# M510A.net
KiCad netlist of a schematic drawn in EAGLE
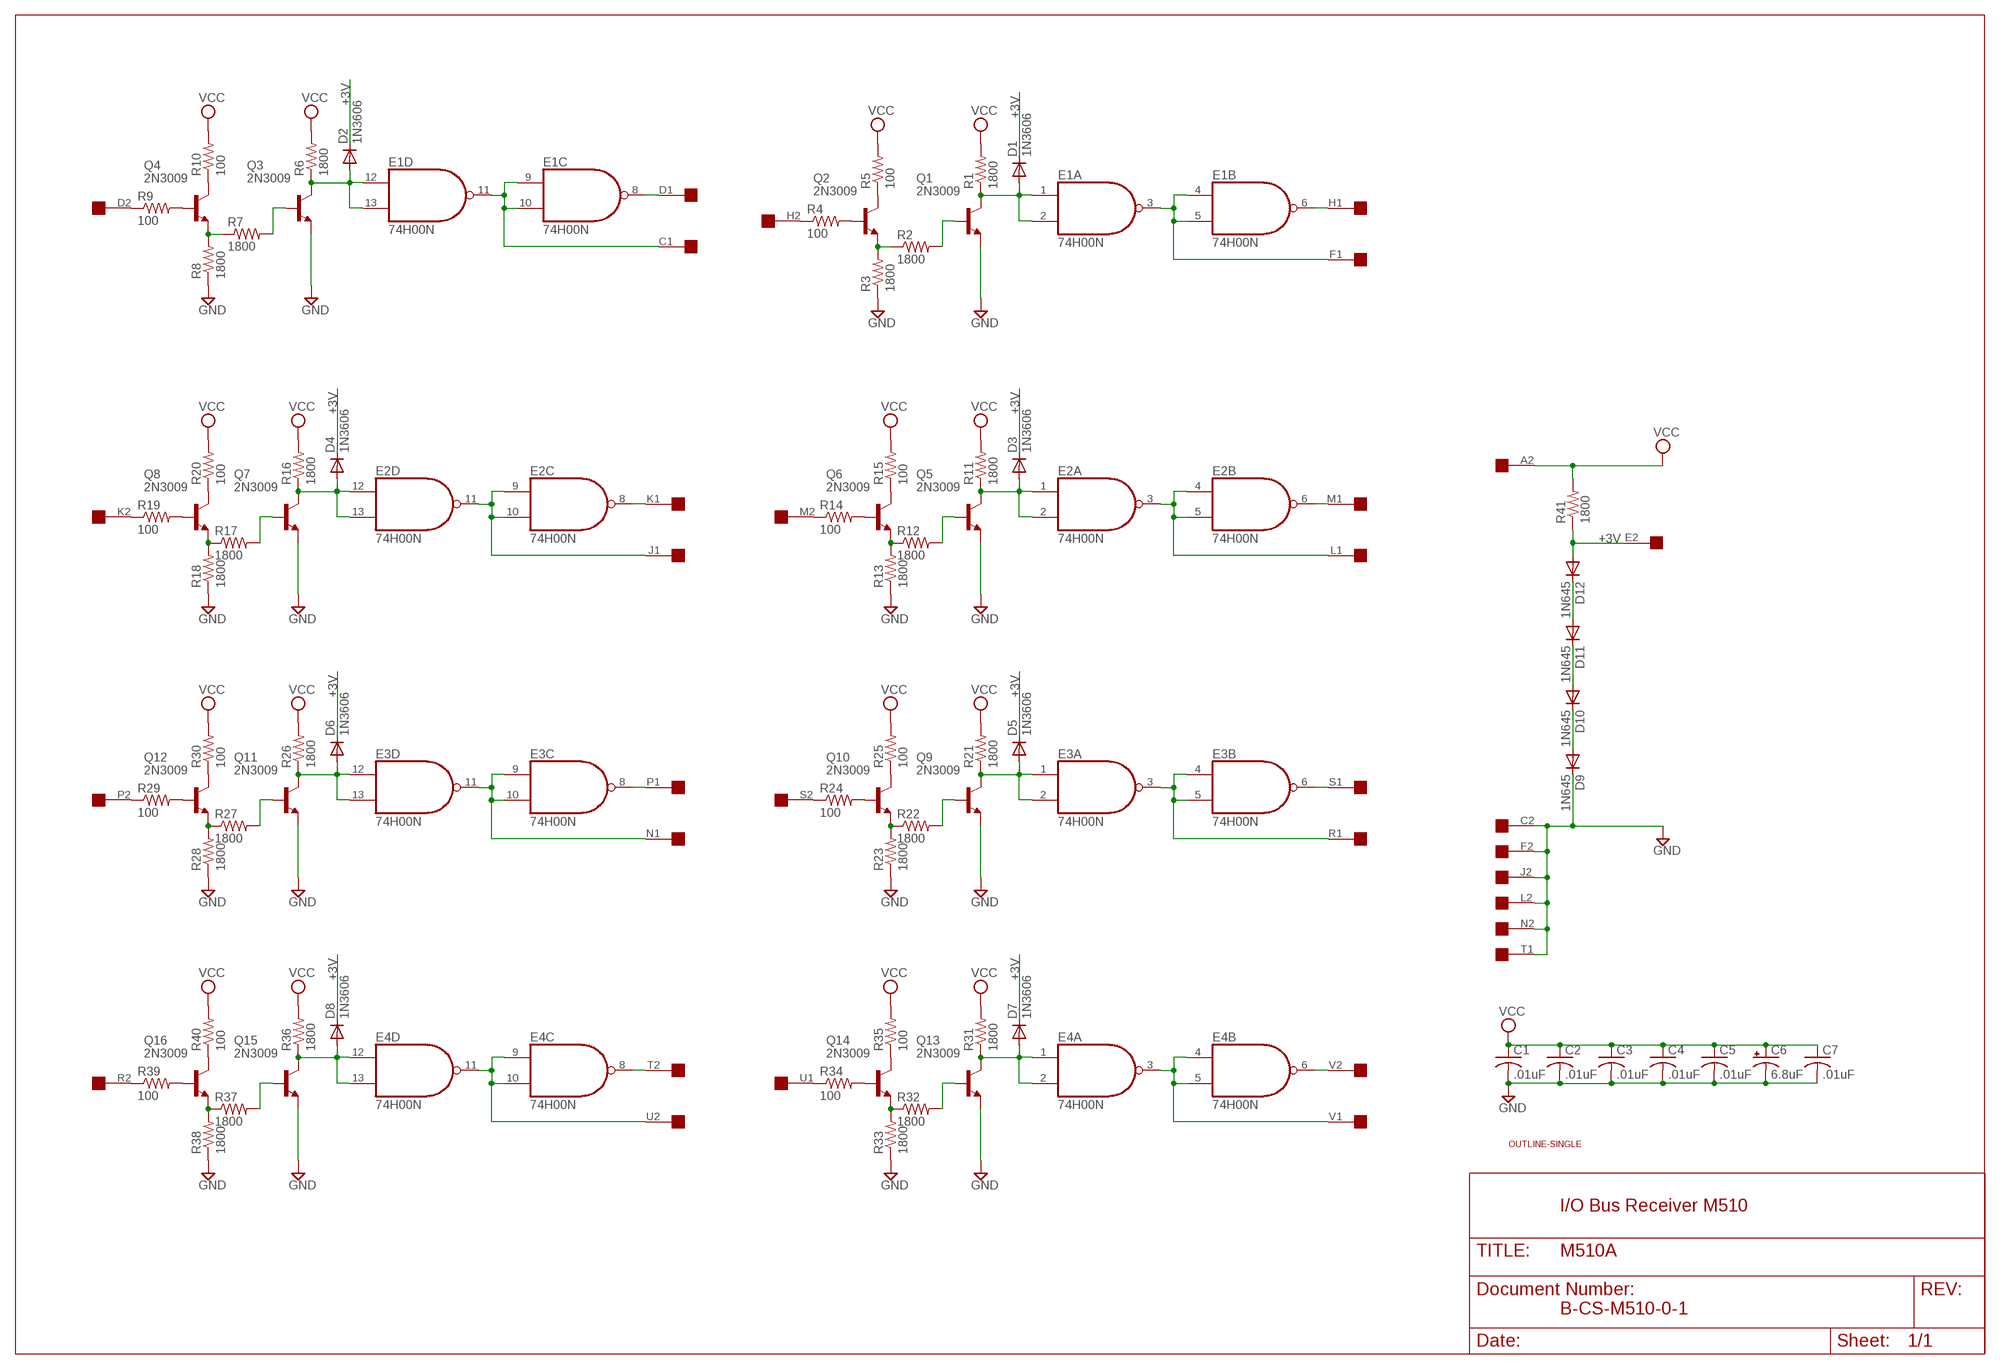
[diagram p0: schematic, sheet 1]

(export (version "E")
  (design (tool "Eeschema 10.0.6"))
  (components
    (comp (ref "C1")
      (value ".01uF")
      (footprint "eagle-import:C050-025X075")
      (libsource (lib "eagle-import") (part "C-US050-025X075"))
    )
    (comp (ref "C2")
      (value ".01uF")
      (footprint "eagle-import:C050-025X075")
      (libsource (lib "eagle-import") (part "C-US050-025X075"))
    )
    (comp (ref "C3")
      (value ".01uF")
      (footprint "eagle-import:C050-025X075")
      (libsource (lib "eagle-import") (part "C-US050-025X075"))
    )
    (comp (ref "C4")
      (value ".01uF")
      (footprint "eagle-import:C050-025X075")
      (libsource (lib "eagle-import") (part "C-US050-025X075"))
    )
    (comp (ref "C5")
      (value ".01uF")
      (footprint "eagle-import:C050-025X075")
      (libsource (lib "eagle-import") (part "C-US050-025X075"))
    )
    (comp (ref "C6")
      (value "6.8uF")
      (footprint "eagle-import:E12-8")
      (libsource (lib "eagle-import") (part "CPOL-USE20-8AXIAL"))
    )
    (comp (ref "C7")
      (value ".01uF")
      (footprint "eagle-import:C050-025X075")
      (libsource (lib "eagle-import") (part "C-US050-025X075"))
    )
    (comp (ref "D1")
      (value "1N3606")
      (footprint "eagle-import:DO35-10")
      (libsource (lib "eagle-import") (part "1N4148DO35-10"))
    )
    (comp (ref "D2")
      (value "1N3606")
      (footprint "eagle-import:DO35-10")
      (libsource (lib "eagle-import") (part "1N4148DO35-10"))
    )
    (comp (ref "D3")
      (value "1N3606")
      (footprint "eagle-import:DO35-10")
      (libsource (lib "eagle-import") (part "1N4148DO35-10"))
    )
    (comp (ref "D4")
      (value "1N3606")
      (footprint "eagle-import:DO35-10")
      (libsource (lib "eagle-import") (part "1N4148DO35-10"))
    )
    (comp (ref "D5")
      (value "1N3606")
      (footprint "eagle-import:DO35-10")
      (libsource (lib "eagle-import") (part "1N4148DO35-10"))
    )
    (comp (ref "D6")
      (value "1N3606")
      (footprint "eagle-import:DO35-10")
      (libsource (lib "eagle-import") (part "1N4148DO35-10"))
    )
    (comp (ref "D7")
      (value "1N3606")
      (footprint "eagle-import:DO35-10")
      (libsource (lib "eagle-import") (part "1N4148DO35-10"))
    )
    (comp (ref "D8")
      (value "1N3606")
      (footprint "eagle-import:DO35-10")
      (libsource (lib "eagle-import") (part "1N4148DO35-10"))
    )
    (comp (ref "D9")
      (value "1N645")
      (footprint "eagle-import:DO35-10")
      (libsource (lib "eagle-import") (part "1N4148DO35-10"))
    )
    (comp (ref "D10")
      (value "1N645")
      (footprint "eagle-import:DO35-10")
      (libsource (lib "eagle-import") (part "1N4148DO35-10"))
    )
    (comp (ref "D11")
      (value "1N645")
      (footprint "eagle-import:DO35-10")
      (libsource (lib "eagle-import") (part "1N4148DO35-10"))
    )
    (comp (ref "D12")
      (value "1N645")
      (footprint "eagle-import:DO35-10")
      (libsource (lib "eagle-import") (part "1N4148DO35-10"))
    )
    (comp (ref "E1")
      (value "74H00N")
      (footprint "eagle-import:DIL14")
      (libsource (lib "eagle-import") (part "7400N"))
    )
    (comp (ref "E2")
      (value "74H00N")
      (footprint "eagle-import:DIL14")
      (libsource (lib "eagle-import") (part "7400N"))
    )
    (comp (ref "E3")
      (value "74H00N")
      (footprint "eagle-import:DIL14")
      (libsource (lib "eagle-import") (part "7400N"))
    )
    (comp (ref "E4")
      (value "74H00N")
      (footprint "eagle-import:DIL14")
      (libsource (lib "eagle-import") (part "7400N"))
    )
    (comp (ref "EDGE1")
      (value "EDGE-2CONNECTOR")
      (footprint "eagle-import:EDGE-CON2")
      (libsource (lib "eagle-import") (part "EDGE-2CONNECTOR"))
    )
    (comp (ref "Q1")
      (value "2N3009")
      (footprint "eagle-import:TO39")
      (libsource (lib "eagle-import") (part "2N3019"))
    )
    (comp (ref "Q2")
      (value "2N3009")
      (footprint "eagle-import:TO39")
      (libsource (lib "eagle-import") (part "2N3019"))
    )
    (comp (ref "Q3")
      (value "2N3009")
      (footprint "eagle-import:TO39")
      (libsource (lib "eagle-import") (part "2N3019"))
    )
    (comp (ref "Q4")
      (value "2N3009")
      (footprint "eagle-import:TO39")
      (libsource (lib "eagle-import") (part "2N3019"))
    )
    (comp (ref "Q5")
      (value "2N3009")
      (footprint "eagle-import:TO39")
      (libsource (lib "eagle-import") (part "2N3019"))
    )
    (comp (ref "Q6")
      (value "2N3009")
      (footprint "eagle-import:TO39")
      (libsource (lib "eagle-import") (part "2N3019"))
    )
    (comp (ref "Q7")
      (value "2N3009")
      (footprint "eagle-import:TO39")
      (libsource (lib "eagle-import") (part "2N3019"))
    )
    (comp (ref "Q8")
      (value "2N3009")
      (footprint "eagle-import:TO39")
      (libsource (lib "eagle-import") (part "2N3019"))
    )
    (comp (ref "Q9")
      (value "2N3009")
      (footprint "eagle-import:TO39")
      (libsource (lib "eagle-import") (part "2N3019"))
    )
    (comp (ref "Q10")
      (value "2N3009")
      (footprint "eagle-import:TO39")
      (libsource (lib "eagle-import") (part "2N3019"))
    )
    (comp (ref "Q11")
      (value "2N3009")
      (footprint "eagle-import:TO39")
      (libsource (lib "eagle-import") (part "2N3019"))
    )
    (comp (ref "Q12")
      (value "2N3009")
      (footprint "eagle-import:TO39")
      (libsource (lib "eagle-import") (part "2N3019"))
    )
    (comp (ref "Q13")
      (value "2N3009")
      (footprint "eagle-import:TO39")
      (libsource (lib "eagle-import") (part "2N3019"))
    )
    (comp (ref "Q14")
      (value "2N3009")
      (footprint "eagle-import:TO39")
      (libsource (lib "eagle-import") (part "2N3019"))
    )
    (comp (ref "Q15")
      (value "2N3009")
      (footprint "eagle-import:TO39")
      (libsource (lib "eagle-import") (part "2N3019"))
    )
    (comp (ref "Q16")
      (value "2N3009")
      (footprint "eagle-import:TO39")
      (libsource (lib "eagle-import") (part "2N3019"))
    )
    (comp (ref "R1")
      (value "1800")
      (footprint "eagle-import:0207_10")
      (libsource (lib "eagle-import") (part "R-US_0207/10"))
    )
    (comp (ref "R2")
      (value "1800")
      (footprint "eagle-import:0207_10")
      (libsource (lib "eagle-import") (part "R-US_0207/10"))
    )
    (comp (ref "R3")
      (value "1800")
      (footprint "eagle-import:0207_10")
      (libsource (lib "eagle-import") (part "R-US_0207/10"))
    )
    (comp (ref "R4")
      (value "100")
      (footprint "eagle-import:0207_10")
      (libsource (lib "eagle-import") (part "R-US_0207/10"))
    )
    (comp (ref "R5")
      (value "100")
      (footprint "eagle-import:0207_10")
      (libsource (lib "eagle-import") (part "R-US_0207/10"))
    )
    (comp (ref "R6")
      (value "1800")
      (footprint "eagle-import:0207_10")
      (libsource (lib "eagle-import") (part "R-US_0207/10"))
    )
    (comp (ref "R7")
      (value "1800")
      (footprint "eagle-import:0207_10")
      (libsource (lib "eagle-import") (part "R-US_0207/10"))
    )
    (comp (ref "R8")
      (value "1800")
      (footprint "eagle-import:0207_10")
      (libsource (lib "eagle-import") (part "R-US_0207/10"))
    )
    (comp (ref "R9")
      (value "100")
      (footprint "eagle-import:0207_10")
      (libsource (lib "eagle-import") (part "R-US_0207/10"))
    )
    (comp (ref "R10")
      (value "100")
      (footprint "eagle-import:0207_10")
      (libsource (lib "eagle-import") (part "R-US_0207/10"))
    )
    (comp (ref "R11")
      (value "1800")
      (footprint "eagle-import:0207_10")
      (libsource (lib "eagle-import") (part "R-US_0207/10"))
    )
    (comp (ref "R12")
      (value "1800")
      (footprint "eagle-import:0207_10")
      (libsource (lib "eagle-import") (part "R-US_0207/10"))
    )
    (comp (ref "R13")
      (value "1800")
      (footprint "eagle-import:0207_10")
      (libsource (lib "eagle-import") (part "R-US_0207/10"))
    )
    (comp (ref "R14")
      (value "100")
      (footprint "eagle-import:0207_10")
      (libsource (lib "eagle-import") (part "R-US_0207/10"))
    )
    (comp (ref "R15")
      (value "100")
      (footprint "eagle-import:0207_10")
      (libsource (lib "eagle-import") (part "R-US_0207/10"))
    )
    (comp (ref "R16")
      (value "1800")
      (footprint "eagle-import:0207_10")
      (libsource (lib "eagle-import") (part "R-US_0207/10"))
    )
    (comp (ref "R17")
      (value "1800")
      (footprint "eagle-import:0207_10")
      (libsource (lib "eagle-import") (part "R-US_0207/10"))
    )
    (comp (ref "R18")
      (value "1800")
      (footprint "eagle-import:0207_10")
      (libsource (lib "eagle-import") (part "R-US_0207/10"))
    )
    (comp (ref "R19")
      (value "100")
      (footprint "eagle-import:0207_10")
      (libsource (lib "eagle-import") (part "R-US_0207/10"))
    )
    (comp (ref "R20")
      (value "100")
      (footprint "eagle-import:0207_10")
      (libsource (lib "eagle-import") (part "R-US_0207/10"))
    )
    (comp (ref "R21")
      (value "1800")
      (footprint "eagle-import:0207_10")
      (libsource (lib "eagle-import") (part "R-US_0207/10"))
    )
    (comp (ref "R22")
      (value "1800")
      (footprint "eagle-import:0207_10")
      (libsource (lib "eagle-import") (part "R-US_0207/10"))
    )
    (comp (ref "R23")
      (value "1800")
      (footprint "eagle-import:0207_10")
      (libsource (lib "eagle-import") (part "R-US_0207/10"))
    )
    (comp (ref "R24")
      (value "100")
      (footprint "eagle-import:0207_10")
      (libsource (lib "eagle-import") (part "R-US_0207/10"))
    )
    (comp (ref "R25")
      (value "100")
      (footprint "eagle-import:0207_10")
      (libsource (lib "eagle-import") (part "R-US_0207/10"))
    )
    (comp (ref "R26")
      (value "1800")
      (footprint "eagle-import:0207_10")
      (libsource (lib "eagle-import") (part "R-US_0207/10"))
    )
    (comp (ref "R27")
      (value "1800")
      (footprint "eagle-import:0207_10")
      (libsource (lib "eagle-import") (part "R-US_0207/10"))
    )
    (comp (ref "R28")
      (value "1800")
      (footprint "eagle-import:0207_10")
      (libsource (lib "eagle-import") (part "R-US_0207/10"))
    )
    (comp (ref "R29")
      (value "100")
      (footprint "eagle-import:0207_10")
      (libsource (lib "eagle-import") (part "R-US_0207/10"))
    )
    (comp (ref "R30")
      (value "100")
      (footprint "eagle-import:0207_10")
      (libsource (lib "eagle-import") (part "R-US_0207/10"))
    )
    (comp (ref "R31")
      (value "1800")
      (footprint "eagle-import:0207_10")
      (libsource (lib "eagle-import") (part "R-US_0207/10"))
    )
    (comp (ref "R32")
      (value "1800")
      (footprint "eagle-import:0207_10")
      (libsource (lib "eagle-import") (part "R-US_0207/10"))
    )
    (comp (ref "R33")
      (value "1800")
      (footprint "eagle-import:0207_10")
      (libsource (lib "eagle-import") (part "R-US_0207/10"))
    )
    (comp (ref "R34")
      (value "100")
      (footprint "eagle-import:0207_10")
      (libsource (lib "eagle-import") (part "R-US_0207/10"))
    )
    (comp (ref "R35")
      (value "100")
      (footprint "eagle-import:0207_10")
      (libsource (lib "eagle-import") (part "R-US_0207/10"))
    )
    (comp (ref "R36")
      (value "1800")
      (footprint "eagle-import:0207_10")
      (libsource (lib "eagle-import") (part "R-US_0207/10"))
    )
    (comp (ref "R37")
      (value "1800")
      (footprint "eagle-import:0207_10")
      (libsource (lib "eagle-import") (part "R-US_0207/10"))
    )
    (comp (ref "R38")
      (value "1800")
      (footprint "eagle-import:0207_10")
      (libsource (lib "eagle-import") (part "R-US_0207/10"))
    )
    (comp (ref "R39")
      (value "100")
      (footprint "eagle-import:0207_10")
      (libsource (lib "eagle-import") (part "R-US_0207/10"))
    )
    (comp (ref "R40")
      (value "100")
      (footprint "eagle-import:0207_10")
      (libsource (lib "eagle-import") (part "R-US_0207/10"))
    )
    (comp (ref "R41")
      (value "1800")
      (footprint "eagle-import:0207_10")
      (libsource (lib "eagle-import") (part "R-US_0207/10"))
    )
    (comp (ref "U$4")
      (value "OUTLINE-SINGLE")
      (footprint "eagle-import:SINGLE")
      (libsource (lib "eagle-import") (part "OUTLINE-SINGLE"))
    )
  )
  (nets
    (net (code "1") (name "/+3V") (class "Default")
      (node (ref "D1") (pin "C") (pinfunction "C_C") (pintype "passive"))
      (node (ref "D12") (pin "A") (pinfunction "A_A") (pintype "passive"))
      (node (ref "D2") (pin "C") (pinfunction "C_C") (pintype "passive"))
      (node (ref "D3") (pin "C") (pinfunction "C_C") (pintype "passive"))
      (node (ref "D4") (pin "C") (pinfunction "C_C") (pintype "passive"))
      (node (ref "D5") (pin "C") (pinfunction "C_C") (pintype "passive"))
      (node (ref "D6") (pin "C") (pinfunction "C_C") (pintype "passive"))
      (node (ref "D7") (pin "C") (pinfunction "C_C") (pintype "passive"))
      (node (ref "D8") (pin "C") (pinfunction "C_C") (pintype "passive"))
      (node (ref "EDGE1") (pin "E2") (pinfunction "1_E2") (pintype "bidirectional"))
      (node (ref "R41") (pin "1") (pinfunction "1_1") (pintype "passive"))
    )
    (net (code "2") (name "GND") (class "Default")
      (node (ref "C1") (pin "2") (pinfunction "2_2") (pintype "passive"))
      (node (ref "C2") (pin "2") (pinfunction "2_2") (pintype "passive"))
      (node (ref "C3") (pin "2") (pinfunction "2_2") (pintype "passive"))
      (node (ref "C4") (pin "2") (pinfunction "2_2") (pintype "passive"))
      (node (ref "C5") (pin "2") (pinfunction "2_2") (pintype "passive"))
      (node (ref "C6") (pin "-") (pinfunction "-_-") (pintype "passive"))
      (node (ref "C7") (pin "2") (pinfunction "2_2") (pintype "passive"))
      (node (ref "D9") (pin "C") (pinfunction "C_C") (pintype "passive"))
      (node (ref "EDGE1") (pin "C2") (pinfunction "1_C2") (pintype "bidirectional"))
      (node (ref "EDGE1") (pin "F2") (pinfunction "1_F2") (pintype "bidirectional"))
      (node (ref "EDGE1") (pin "J2") (pinfunction "1_J2") (pintype "bidirectional"))
      (node (ref "EDGE1") (pin "L2") (pinfunction "1_L2") (pintype "bidirectional"))
      (node (ref "EDGE1") (pin "N2") (pinfunction "1_N2") (pintype "bidirectional"))
      (node (ref "EDGE1") (pin "T1") (pinfunction "1_T1") (pintype "bidirectional"))
      (node (ref "Q1") (pin "1") (pinfunction "E_1") (pintype "passive"))
      (node (ref "Q11") (pin "1") (pinfunction "E_1") (pintype "passive"))
      (node (ref "Q13") (pin "1") (pinfunction "E_1") (pintype "passive"))
      (node (ref "Q15") (pin "1") (pinfunction "E_1") (pintype "passive"))
      (node (ref "Q3") (pin "1") (pinfunction "E_1") (pintype "passive"))
      (node (ref "Q5") (pin "1") (pinfunction "E_1") (pintype "passive"))
      (node (ref "Q7") (pin "1") (pinfunction "E_1") (pintype "passive"))
      (node (ref "Q9") (pin "1") (pinfunction "E_1") (pintype "passive"))
      (node (ref "R13") (pin "1") (pinfunction "1_1") (pintype "passive"))
      (node (ref "R18") (pin "1") (pinfunction "1_1") (pintype "passive"))
      (node (ref "R23") (pin "1") (pinfunction "1_1") (pintype "passive"))
      (node (ref "R28") (pin "1") (pinfunction "1_1") (pintype "passive"))
      (node (ref "R3") (pin "1") (pinfunction "1_1") (pintype "passive"))
      (node (ref "R33") (pin "1") (pinfunction "1_1") (pintype "passive"))
      (node (ref "R38") (pin "1") (pinfunction "1_1") (pintype "passive"))
      (node (ref "R8") (pin "1") (pinfunction "1_1") (pintype "passive"))
    )
    (net (code "3") (name "Net-(D10-PadA)") (class "Default")
      (node (ref "D10") (pin "A") (pinfunction "A_A") (pintype "passive"))
      (node (ref "D11") (pin "C") (pinfunction "C_C") (pintype "passive"))
    )
    (net (code "4") (name "Net-(D10-PadC)") (class "Default")
      (node (ref "D10") (pin "C") (pinfunction "C_C") (pintype "passive"))
      (node (ref "D9") (pin "A") (pinfunction "A_A") (pintype "passive"))
    )
    (net (code "5") (name "Net-(D11-PadA)") (class "Default")
      (node (ref "D11") (pin "A") (pinfunction "A_A") (pintype "passive"))
      (node (ref "D12") (pin "C") (pinfunction "C_C") (pintype "passive"))
    )
    (net (code "6") (name "Net-(E1A-I0)") (class "Default")
      (node (ref "D1") (pin "A") (pinfunction "A_A") (pintype "passive"))
      (node (ref "E1") (pin "1") (pinfunction "I0_1") (pintype "input"))
      (node (ref "E1") (pin "2") (pinfunction "I1_2") (pintype "input"))
      (node (ref "Q1") (pin "3") (pinfunction "C_3") (pintype "passive"))
      (node (ref "R1") (pin "1") (pinfunction "1_1") (pintype "passive"))
    )
    (net (code "7") (name "Net-(E1A-O)") (class "Default")
      (node (ref "E1") (pin "3") (pinfunction "O_3") (pintype "output"))
      (node (ref "E1") (pin "4") (pinfunction "I0_4") (pintype "input"))
      (node (ref "E1") (pin "5") (pinfunction "I1_5") (pintype "input"))
      (node (ref "EDGE1") (pin "F1") (pinfunction "1_F1") (pintype "bidirectional"))
    )
    (net (code "8") (name "Net-(E1B-O)") (class "Default")
      (node (ref "E1") (pin "6") (pinfunction "O_6") (pintype "output"))
      (node (ref "EDGE1") (pin "H1") (pinfunction "1_H1") (pintype "bidirectional"))
    )
    (net (code "9") (name "Net-(E1C-I0)") (class "Default")
      (node (ref "E1") (pin "10") (pinfunction "I1_10") (pintype "input"))
      (node (ref "E1") (pin "11") (pinfunction "O_11") (pintype "output"))
      (node (ref "E1") (pin "9") (pinfunction "I0_9") (pintype "input"))
      (node (ref "EDGE1") (pin "C1") (pinfunction "1_C1") (pintype "bidirectional"))
    )
    (net (code "10") (name "Net-(E1C-O)") (class "Default")
      (node (ref "E1") (pin "8") (pinfunction "O_8") (pintype "output"))
      (node (ref "EDGE1") (pin "D1") (pinfunction "1_D1") (pintype "bidirectional"))
    )
    (net (code "11") (name "Net-(E1D-I0)") (class "Default")
      (node (ref "D2") (pin "A") (pinfunction "A_A") (pintype "passive"))
      (node (ref "E1") (pin "12") (pinfunction "I0_12") (pintype "input"))
      (node (ref "E1") (pin "13") (pinfunction "I1_13") (pintype "input"))
      (node (ref "Q3") (pin "3") (pinfunction "C_3") (pintype "passive"))
      (node (ref "R6") (pin "1") (pinfunction "1_1") (pintype "passive"))
    )
    (net (code "12") (name "Net-(E2A-I0)") (class "Default")
      (node (ref "D3") (pin "A") (pinfunction "A_A") (pintype "passive"))
      (node (ref "E2") (pin "1") (pinfunction "I0_1") (pintype "input"))
      (node (ref "E2") (pin "2") (pinfunction "I1_2") (pintype "input"))
      (node (ref "Q5") (pin "3") (pinfunction "C_3") (pintype "passive"))
      (node (ref "R11") (pin "1") (pinfunction "1_1") (pintype "passive"))
    )
    (net (code "13") (name "Net-(E2A-O)") (class "Default")
      (node (ref "E2") (pin "3") (pinfunction "O_3") (pintype "output"))
      (node (ref "E2") (pin "4") (pinfunction "I0_4") (pintype "input"))
      (node (ref "E2") (pin "5") (pinfunction "I1_5") (pintype "input"))
      (node (ref "EDGE1") (pin "L1") (pinfunction "1_L1") (pintype "bidirectional"))
    )
    (net (code "14") (name "Net-(E2B-O)") (class "Default")
      (node (ref "E2") (pin "6") (pinfunction "O_6") (pintype "output"))
      (node (ref "EDGE1") (pin "M1") (pinfunction "1_M1") (pintype "bidirectional"))
    )
    (net (code "15") (name "Net-(E2C-I0)") (class "Default")
      (node (ref "E2") (pin "10") (pinfunction "I1_10") (pintype "input"))
      (node (ref "E2") (pin "11") (pinfunction "O_11") (pintype "output"))
      (node (ref "E2") (pin "9") (pinfunction "I0_9") (pintype "input"))
      (node (ref "EDGE1") (pin "J1") (pinfunction "1_J1") (pintype "bidirectional"))
    )
    (net (code "16") (name "Net-(E2C-O)") (class "Default")
      (node (ref "E2") (pin "8") (pinfunction "O_8") (pintype "output"))
      (node (ref "EDGE1") (pin "K1") (pinfunction "1_K1") (pintype "bidirectional"))
    )
    (net (code "17") (name "Net-(E2D-I0)") (class "Default")
      (node (ref "D4") (pin "A") (pinfunction "A_A") (pintype "passive"))
      (node (ref "E2") (pin "12") (pinfunction "I0_12") (pintype "input"))
      (node (ref "E2") (pin "13") (pinfunction "I1_13") (pintype "input"))
      (node (ref "Q7") (pin "3") (pinfunction "C_3") (pintype "passive"))
      (node (ref "R16") (pin "1") (pinfunction "1_1") (pintype "passive"))
    )
    (net (code "18") (name "Net-(E3A-I0)") (class "Default")
      (node (ref "D5") (pin "A") (pinfunction "A_A") (pintype "passive"))
      (node (ref "E3") (pin "1") (pinfunction "I0_1") (pintype "input"))
      (node (ref "E3") (pin "2") (pinfunction "I1_2") (pintype "input"))
      (node (ref "Q9") (pin "3") (pinfunction "C_3") (pintype "passive"))
      (node (ref "R21") (pin "1") (pinfunction "1_1") (pintype "passive"))
    )
    (net (code "19") (name "Net-(E3A-O)") (class "Default")
      (node (ref "E3") (pin "3") (pinfunction "O_3") (pintype "output"))
      (node (ref "E3") (pin "4") (pinfunction "I0_4") (pintype "input"))
      (node (ref "E3") (pin "5") (pinfunction "I1_5") (pintype "input"))
      (node (ref "EDGE1") (pin "R1") (pinfunction "1_R1") (pintype "bidirectional"))
    )
    (net (code "20") (name "Net-(E3B-O)") (class "Default")
      (node (ref "E3") (pin "6") (pinfunction "O_6") (pintype "output"))
      (node (ref "EDGE1") (pin "S1") (pinfunction "1_S1") (pintype "bidirectional"))
    )
    (net (code "21") (name "Net-(E3C-I0)") (class "Default")
      (node (ref "E3") (pin "10") (pinfunction "I1_10") (pintype "input"))
      (node (ref "E3") (pin "11") (pinfunction "O_11") (pintype "output"))
      (node (ref "E3") (pin "9") (pinfunction "I0_9") (pintype "input"))
      (node (ref "EDGE1") (pin "N1") (pinfunction "1_N1") (pintype "bidirectional"))
    )
    (net (code "22") (name "Net-(E3C-O)") (class "Default")
      (node (ref "E3") (pin "8") (pinfunction "O_8") (pintype "output"))
      (node (ref "EDGE1") (pin "P1") (pinfunction "1_P1") (pintype "bidirectional"))
    )
    (net (code "23") (name "Net-(E3D-I0)") (class "Default")
      (node (ref "D6") (pin "A") (pinfunction "A_A") (pintype "passive"))
      (node (ref "E3") (pin "12") (pinfunction "I0_12") (pintype "input"))
      (node (ref "E3") (pin "13") (pinfunction "I1_13") (pintype "input"))
      (node (ref "Q11") (pin "3") (pinfunction "C_3") (pintype "passive"))
      (node (ref "R26") (pin "1") (pinfunction "1_1") (pintype "passive"))
    )
    (net (code "24") (name "Net-(E4A-I0)") (class "Default")
      (node (ref "D7") (pin "A") (pinfunction "A_A") (pintype "passive"))
      (node (ref "E4") (pin "1") (pinfunction "I0_1") (pintype "input"))
      (node (ref "E4") (pin "2") (pinfunction "I1_2") (pintype "input"))
      (node (ref "Q13") (pin "3") (pinfunction "C_3") (pintype "passive"))
      (node (ref "R31") (pin "1") (pinfunction "1_1") (pintype "passive"))
    )
    (net (code "25") (name "Net-(E4A-O)") (class "Default")
      (node (ref "E4") (pin "3") (pinfunction "O_3") (pintype "output"))
      (node (ref "E4") (pin "4") (pinfunction "I0_4") (pintype "input"))
      (node (ref "E4") (pin "5") (pinfunction "I1_5") (pintype "input"))
      (node (ref "EDGE1") (pin "V1") (pinfunction "1_V1") (pintype "bidirectional"))
    )
    (net (code "26") (name "Net-(E4B-O)") (class "Default")
      (node (ref "E4") (pin "6") (pinfunction "O_6") (pintype "output"))
      (node (ref "EDGE1") (pin "V2") (pinfunction "1_V2") (pintype "bidirectional"))
    )
    (net (code "27") (name "Net-(E4C-I0)") (class "Default")
      (node (ref "E4") (pin "10") (pinfunction "I1_10") (pintype "input"))
      (node (ref "E4") (pin "11") (pinfunction "O_11") (pintype "output"))
      (node (ref "E4") (pin "9") (pinfunction "I0_9") (pintype "input"))
      (node (ref "EDGE1") (pin "U2") (pinfunction "1_U2") (pintype "bidirectional"))
    )
    (net (code "28") (name "Net-(E4C-O)") (class "Default")
      (node (ref "E4") (pin "8") (pinfunction "O_8") (pintype "output"))
      (node (ref "EDGE1") (pin "T2") (pinfunction "1_T2") (pintype "bidirectional"))
    )
    (net (code "29") (name "Net-(E4D-I0)") (class "Default")
      (node (ref "D8") (pin "A") (pinfunction "A_A") (pintype "passive"))
      (node (ref "E4") (pin "12") (pinfunction "I0_12") (pintype "input"))
      (node (ref "E4") (pin "13") (pinfunction "I1_13") (pintype "input"))
      (node (ref "Q15") (pin "3") (pinfunction "C_3") (pintype "passive"))
      (node (ref "R36") (pin "1") (pinfunction "1_1") (pintype "passive"))
    )
    (net (code "30") (name "Net-(EDGE1AB-1)") (class "Default")
      (node (ref "EDGE1") (pin "R2") (pinfunction "1_R2") (pintype "bidirectional"))
      (node (ref "R39") (pin "1") (pinfunction "1_1") (pintype "passive"))
    )
    (net (code "31") (name "Net-(EDGE1AD-1)") (class "Default")
      (node (ref "EDGE1") (pin "S2") (pinfunction "1_S2") (pintype "bidirectional"))
      (node (ref "R24") (pin "1") (pinfunction "1_1") (pintype "passive"))
    )
    (net (code "32") (name "Net-(EDGE1AG-1)") (class "Default")
      (node (ref "EDGE1") (pin "U1") (pinfunction "1_U1") (pintype "bidirectional"))
      (node (ref "R34") (pin "1") (pinfunction "1_1") (pintype "passive"))
    )
    (net (code "33") (name "Net-(EDGE1H-1)") (class "Default")
      (node (ref "EDGE1") (pin "D2") (pinfunction "1_D2") (pintype "bidirectional"))
      (node (ref "R9") (pin "1") (pinfunction "1_1") (pintype "passive"))
    )
    (net (code "34") (name "Net-(EDGE1N-1)") (class "Default")
      (node (ref "EDGE1") (pin "H2") (pinfunction "1_H2") (pintype "bidirectional"))
      (node (ref "R4") (pin "1") (pinfunction "1_1") (pintype "passive"))
    )
    (net (code "35") (name "Net-(EDGE1R-1)") (class "Default")
      (node (ref "EDGE1") (pin "K2") (pinfunction "1_K2") (pintype "bidirectional"))
      (node (ref "R19") (pin "1") (pinfunction "1_1") (pintype "passive"))
    )
    (net (code "36") (name "Net-(EDGE1V-1)") (class "Default")
      (node (ref "EDGE1") (pin "M2") (pinfunction "1_M2") (pintype "bidirectional"))
      (node (ref "R14") (pin "1") (pinfunction "1_1") (pintype "passive"))
    )
    (net (code "37") (name "Net-(EDGE1Z-1)") (class "Default")
      (node (ref "EDGE1") (pin "P2") (pinfunction "1_P2") (pintype "bidirectional"))
      (node (ref "R29") (pin "1") (pinfunction "1_1") (pintype "passive"))
    )
    (net (code "38") (name "Net-(Q1-B)") (class "Default")
      (node (ref "Q1") (pin "2") (pinfunction "B_2") (pintype "passive"))
      (node (ref "R2") (pin "2") (pinfunction "2_2") (pintype "passive"))
    )
    (net (code "39") (name "Net-(Q2-B)") (class "Default")
      (node (ref "Q2") (pin "2") (pinfunction "B_2") (pintype "passive"))
      (node (ref "R4") (pin "2") (pinfunction "2_2") (pintype "passive"))
    )
    (net (code "40") (name "Net-(Q2-C)") (class "Default")
      (node (ref "Q2") (pin "3") (pinfunction "C_3") (pintype "passive"))
      (node (ref "R5") (pin "1") (pinfunction "1_1") (pintype "passive"))
    )
    (net (code "41") (name "Net-(Q2-E)") (class "Default")
      (node (ref "Q2") (pin "1") (pinfunction "E_1") (pintype "passive"))
      (node (ref "R2") (pin "1") (pinfunction "1_1") (pintype "passive"))
      (node (ref "R3") (pin "2") (pinfunction "2_2") (pintype "passive"))
    )
    (net (code "42") (name "Net-(Q3-B)") (class "Default")
      (node (ref "Q3") (pin "2") (pinfunction "B_2") (pintype "passive"))
      (node (ref "R7") (pin "2") (pinfunction "2_2") (pintype "passive"))
    )
    (net (code "43") (name "Net-(Q4-B)") (class "Default")
      (node (ref "Q4") (pin "2") (pinfunction "B_2") (pintype "passive"))
      (node (ref "R9") (pin "2") (pinfunction "2_2") (pintype "passive"))
    )
    (net (code "44") (name "Net-(Q4-C)") (class "Default")
      (node (ref "Q4") (pin "3") (pinfunction "C_3") (pintype "passive"))
      (node (ref "R10") (pin "1") (pinfunction "1_1") (pintype "passive"))
    )
    (net (code "45") (name "Net-(Q4-E)") (class "Default")
      (node (ref "Q4") (pin "1") (pinfunction "E_1") (pintype "passive"))
      (node (ref "R7") (pin "1") (pinfunction "1_1") (pintype "passive"))
      (node (ref "R8") (pin "2") (pinfunction "2_2") (pintype "passive"))
    )
    (net (code "46") (name "Net-(Q5-B)") (class "Default")
      (node (ref "Q5") (pin "2") (pinfunction "B_2") (pintype "passive"))
      (node (ref "R12") (pin "2") (pinfunction "2_2") (pintype "passive"))
    )
    (net (code "47") (name "Net-(Q6-B)") (class "Default")
      (node (ref "Q6") (pin "2") (pinfunction "B_2") (pintype "passive"))
      (node (ref "R14") (pin "2") (pinfunction "2_2") (pintype "passive"))
    )
    (net (code "48") (name "Net-(Q6-C)") (class "Default")
      (node (ref "Q6") (pin "3") (pinfunction "C_3") (pintype "passive"))
      (node (ref "R15") (pin "1") (pinfunction "1_1") (pintype "passive"))
    )
    (net (code "49") (name "Net-(Q6-E)") (class "Default")
      (node (ref "Q6") (pin "1") (pinfunction "E_1") (pintype "passive"))
      (node (ref "R12") (pin "1") (pinfunction "1_1") (pintype "passive"))
      (node (ref "R13") (pin "2") (pinfunction "2_2") (pintype "passive"))
    )
    (net (code "50") (name "Net-(Q7-B)") (class "Default")
      (node (ref "Q7") (pin "2") (pinfunction "B_2") (pintype "passive"))
      (node (ref "R17") (pin "2") (pinfunction "2_2") (pintype "passive"))
    )
    (net (code "51") (name "Net-(Q8-B)") (class "Default")
      (node (ref "Q8") (pin "2") (pinfunction "B_2") (pintype "passive"))
      (node (ref "R19") (pin "2") (pinfunction "2_2") (pintype "passive"))
    )
    (net (code "52") (name "Net-(Q8-C)") (class "Default")
      (node (ref "Q8") (pin "3") (pinfunction "C_3") (pintype "passive"))
      (node (ref "R20") (pin "1") (pinfunction "1_1") (pintype "passive"))
    )
    (net (code "53") (name "Net-(Q8-E)") (class "Default")
      (node (ref "Q8") (pin "1") (pinfunction "E_1") (pintype "passive"))
      (node (ref "R17") (pin "1") (pinfunction "1_1") (pintype "passive"))
      (node (ref "R18") (pin "2") (pinfunction "2_2") (pintype "passive"))
    )
    (net (code "54") (name "Net-(Q9-B)") (class "Default")
      (node (ref "Q9") (pin "2") (pinfunction "B_2") (pintype "passive"))
      (node (ref "R22") (pin "2") (pinfunction "2_2") (pintype "passive"))
    )
    (net (code "55") (name "Net-(Q10-B)") (class "Default")
      (node (ref "Q10") (pin "2") (pinfunction "B_2") (pintype "passive"))
      (node (ref "R24") (pin "2") (pinfunction "2_2") (pintype "passive"))
    )
    (net (code "56") (name "Net-(Q10-C)") (class "Default")
      (node (ref "Q10") (pin "3") (pinfunction "C_3") (pintype "passive"))
      (node (ref "R25") (pin "1") (pinfunction "1_1") (pintype "passive"))
    )
    (net (code "57") (name "Net-(Q10-E)") (class "Default")
      (node (ref "Q10") (pin "1") (pinfunction "E_1") (pintype "passive"))
      (node (ref "R22") (pin "1") (pinfunction "1_1") (pintype "passive"))
      (node (ref "R23") (pin "2") (pinfunction "2_2") (pintype "passive"))
    )
    (net (code "58") (name "Net-(Q11-B)") (class "Default")
      (node (ref "Q11") (pin "2") (pinfunction "B_2") (pintype "passive"))
      (node (ref "R27") (pin "2") (pinfunction "2_2") (pintype "passive"))
    )
    (net (code "59") (name "Net-(Q12-B)") (class "Default")
      (node (ref "Q12") (pin "2") (pinfunction "B_2") (pintype "passive"))
      (node (ref "R29") (pin "2") (pinfunction "2_2") (pintype "passive"))
    )
    (net (code "60") (name "Net-(Q12-C)") (class "Default")
      (node (ref "Q12") (pin "3") (pinfunction "C_3") (pintype "passive"))
      (node (ref "R30") (pin "1") (pinfunction "1_1") (pintype "passive"))
    )
    (net (code "61") (name "Net-(Q12-E)") (class "Default")
      (node (ref "Q12") (pin "1") (pinfunction "E_1") (pintype "passive"))
      (node (ref "R27") (pin "1") (pinfunction "1_1") (pintype "passive"))
      (node (ref "R28") (pin "2") (pinfunction "2_2") (pintype "passive"))
    )
    (net (code "62") (name "Net-(Q13-B)") (class "Default")
      (node (ref "Q13") (pin "2") (pinfunction "B_2") (pintype "passive"))
      (node (ref "R32") (pin "2") (pinfunction "2_2") (pintype "passive"))
    )
    (net (code "63") (name "Net-(Q14-B)") (class "Default")
      (node (ref "Q14") (pin "2") (pinfunction "B_2") (pintype "passive"))
      (node (ref "R34") (pin "2") (pinfunction "2_2") (pintype "passive"))
    )
    (net (code "64") (name "Net-(Q14-C)") (class "Default")
      (node (ref "Q14") (pin "3") (pinfunction "C_3") (pintype "passive"))
      (node (ref "R35") (pin "1") (pinfunction "1_1") (pintype "passive"))
    )
    (net (code "65") (name "Net-(Q14-E)") (class "Default")
      (node (ref "Q14") (pin "1") (pinfunction "E_1") (pintype "passive"))
      (node (ref "R32") (pin "1") (pinfunction "1_1") (pintype "passive"))
      (node (ref "R33") (pin "2") (pinfunction "2_2") (pintype "passive"))
    )
    (net (code "66") (name "Net-(Q15-B)") (class "Default")
      (node (ref "Q15") (pin "2") (pinfunction "B_2") (pintype "passive"))
      (node (ref "R37") (pin "2") (pinfunction "2_2") (pintype "passive"))
    )
    (net (code "67") (name "Net-(Q16-B)") (class "Default")
      (node (ref "Q16") (pin "2") (pinfunction "B_2") (pintype "passive"))
      (node (ref "R39") (pin "2") (pinfunction "2_2") (pintype "passive"))
    )
    (net (code "68") (name "Net-(Q16-C)") (class "Default")
      (node (ref "Q16") (pin "3") (pinfunction "C_3") (pintype "passive"))
      (node (ref "R40") (pin "1") (pinfunction "1_1") (pintype "passive"))
    )
    (net (code "69") (name "Net-(Q16-E)") (class "Default")
      (node (ref "Q16") (pin "1") (pinfunction "E_1") (pintype "passive"))
      (node (ref "R37") (pin "1") (pinfunction "1_1") (pintype "passive"))
      (node (ref "R38") (pin "2") (pinfunction "2_2") (pintype "passive"))
    )
    (net (code "70") (name "VCC") (class "Default")
      (node (ref "C1") (pin "1") (pinfunction "1_1") (pintype "passive"))
      (node (ref "C2") (pin "1") (pinfunction "1_1") (pintype "passive"))
      (node (ref "C3") (pin "1") (pinfunction "1_1") (pintype "passive"))
      (node (ref "C4") (pin "1") (pinfunction "1_1") (pintype "passive"))
      (node (ref "C5") (pin "1") (pinfunction "1_1") (pintype "passive"))
      (node (ref "C6") (pin "+") (pinfunction "+_+") (pintype "passive"))
      (node (ref "C7") (pin "1") (pinfunction "1_1") (pintype "passive"))
      (node (ref "EDGE1") (pin "A2") (pinfunction "1_A2") (pintype "bidirectional"))
      (node (ref "R1") (pin "2") (pinfunction "2_2") (pintype "passive"))
      (node (ref "R10") (pin "2") (pinfunction "2_2") (pintype "passive"))
      (node (ref "R11") (pin "2") (pinfunction "2_2") (pintype "passive"))
      (node (ref "R15") (pin "2") (pinfunction "2_2") (pintype "passive"))
      (node (ref "R16") (pin "2") (pinfunction "2_2") (pintype "passive"))
      (node (ref "R20") (pin "2") (pinfunction "2_2") (pintype "passive"))
      (node (ref "R21") (pin "2") (pinfunction "2_2") (pintype "passive"))
      (node (ref "R25") (pin "2") (pinfunction "2_2") (pintype "passive"))
      (node (ref "R26") (pin "2") (pinfunction "2_2") (pintype "passive"))
      (node (ref "R30") (pin "2") (pinfunction "2_2") (pintype "passive"))
      (node (ref "R31") (pin "2") (pinfunction "2_2") (pintype "passive"))
      (node (ref "R35") (pin "2") (pinfunction "2_2") (pintype "passive"))
      (node (ref "R36") (pin "2") (pinfunction "2_2") (pintype "passive"))
      (node (ref "R40") (pin "2") (pinfunction "2_2") (pintype "passive"))
      (node (ref "R41") (pin "2") (pinfunction "2_2") (pintype "passive"))
      (node (ref "R5") (pin "2") (pinfunction "2_2") (pintype "passive"))
      (node (ref "R6") (pin "2") (pinfunction "2_2") (pintype "passive"))
    )
  )
)
